# dust_environment_sensor_v2.net
KiCad netlist of a schematic drawn in EAGLE
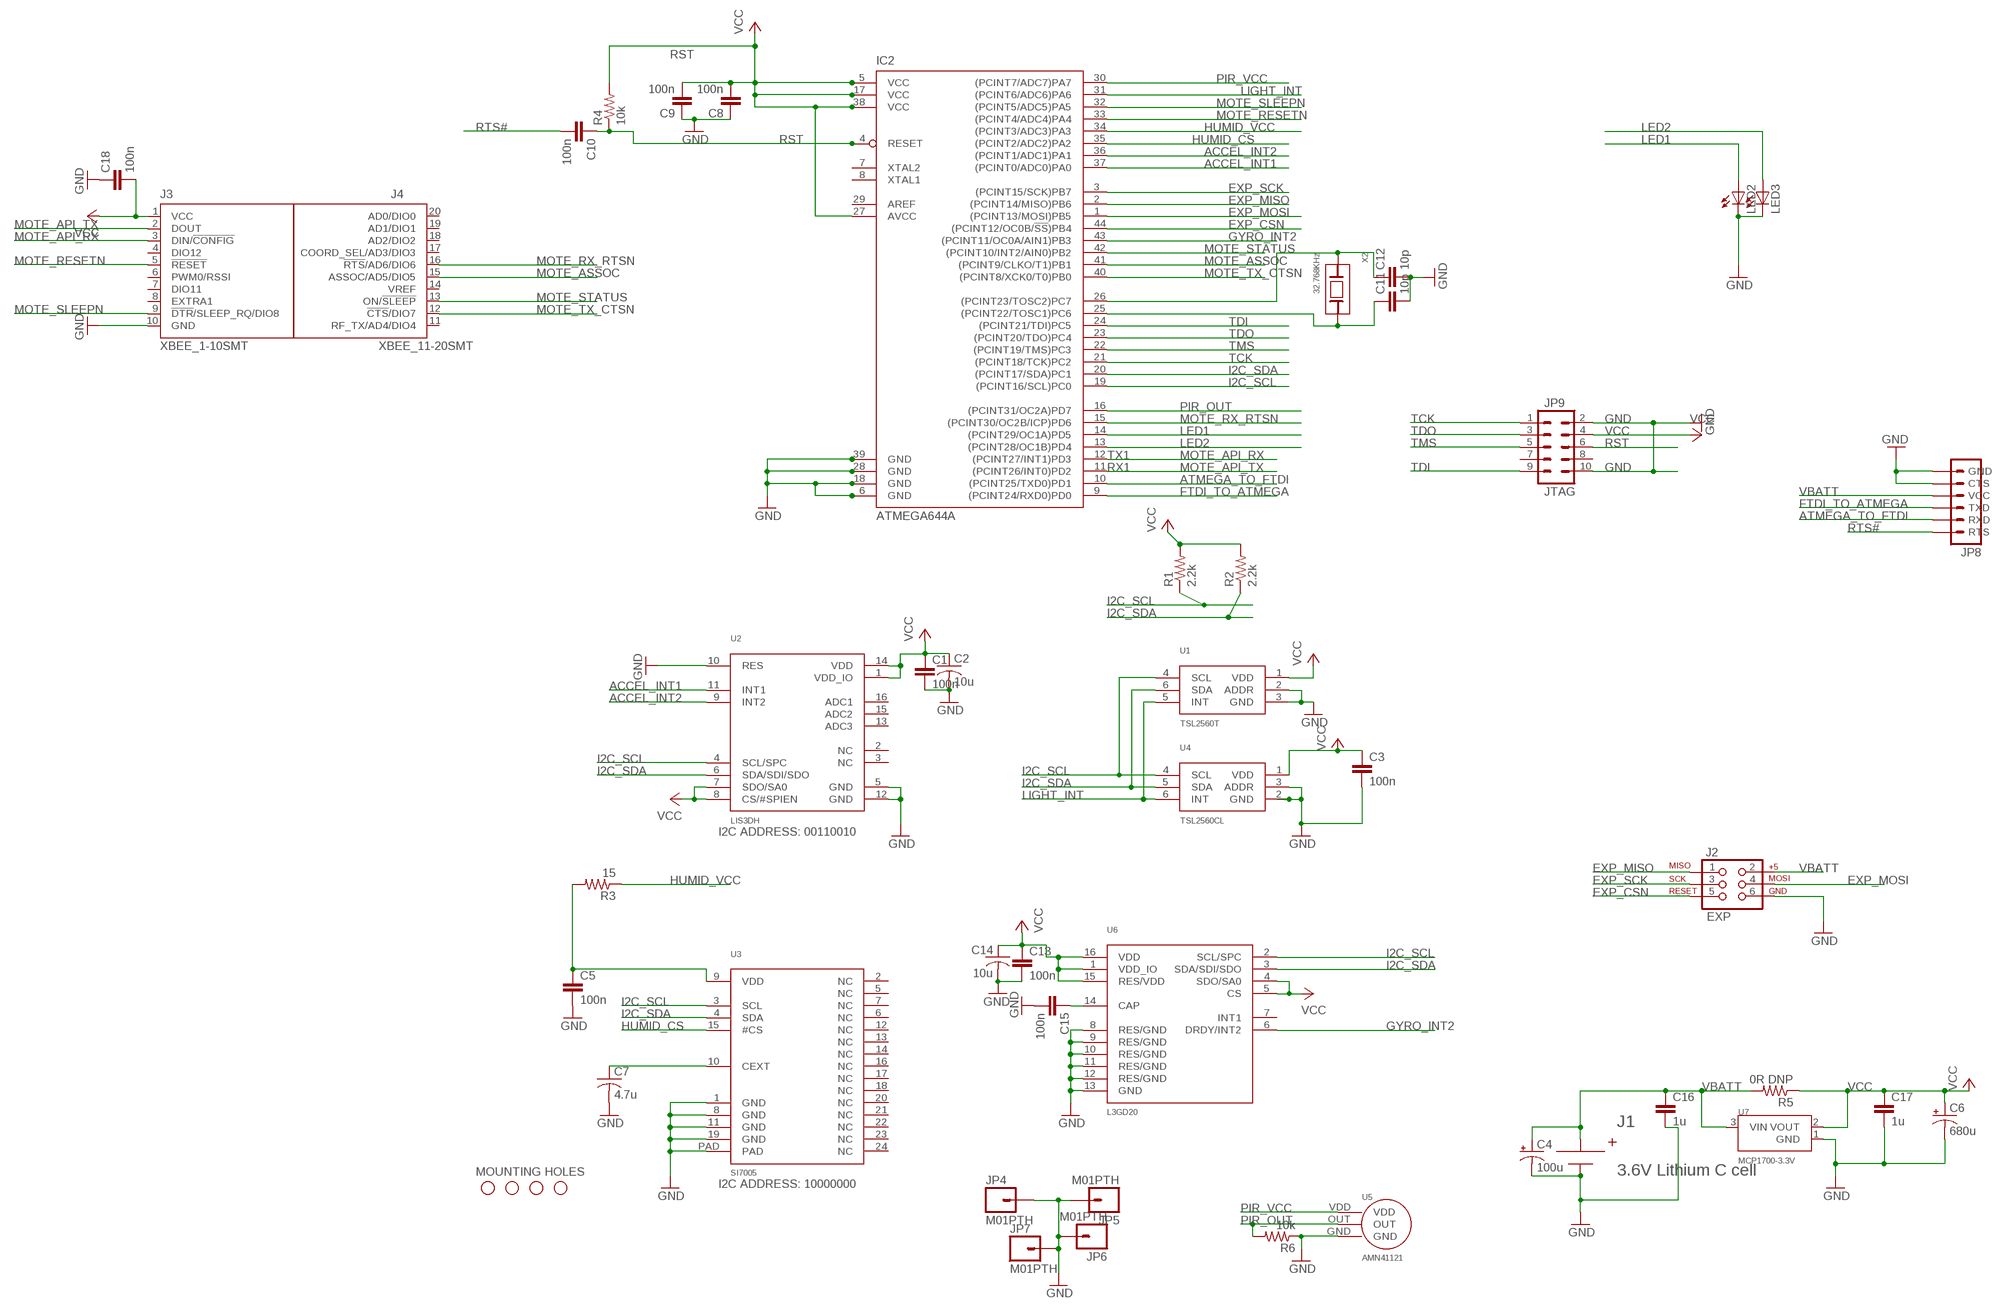
[diagram p0: schematic, sheet 1]

(export (version "E")
  (design (tool "Eeschema 10.0.6"))
  (components
    (comp (ref "C1")
      (value "100n")
      (footprint "eagle-import:C0603")
      (libsource (lib "eagle-import") (part "C-EUC0603"))
    )
    (comp (ref "C2")
      (value "10u")
      (footprint "eagle-import:C0603")
      (libsource (lib "eagle-import") (part "C-USC0603"))
    )
    (comp (ref "C3")
      (value "100n")
      (footprint "eagle-import:C0603")
      (libsource (lib "eagle-import") (part "C-EUC0603"))
    )
    (comp (ref "C4")
      (value "100u")
      (footprint "eagle-import:EIA3216-KIT")
      (libsource (lib "eagle-import") (part "CAP_POL1206-KIT"))
    )
    (comp (ref "C5")
      (value "100n")
      (footprint "eagle-import:C0603")
      (libsource (lib "eagle-import") (part "C-EUC0603"))
    )
    (comp (ref "C6")
      (value "680u")
      (footprint "eagle-import:EIA7343")
      (libsource (lib "eagle-import") (part "CAP_POL7343"))
    )
    (comp (ref "C7")
      (value "4.7u")
      (footprint "eagle-import:C0603")
      (libsource (lib "eagle-import") (part "C-USC0603"))
    )
    (comp (ref "C8")
      (value "100n")
      (footprint "eagle-import:C0603")
      (libsource (lib "eagle-import") (part "C-EUC0603"))
    )
    (comp (ref "C9")
      (value "100n")
      (footprint "eagle-import:C0603")
      (libsource (lib "eagle-import") (part "C-EUC0603"))
    )
    (comp (ref "C10")
      (value "100n")
      (footprint "eagle-import:C0603")
      (libsource (lib "eagle-import") (part "C-EUC0603"))
    )
    (comp (ref "C11")
      (value "10p")
      (footprint "eagle-import:C0603")
      (libsource (lib "eagle-import") (part "C-EUC0603"))
    )
    (comp (ref "C12")
      (value "10p")
      (footprint "eagle-import:C0603")
      (libsource (lib "eagle-import") (part "C-EUC0603"))
    )
    (comp (ref "C13")
      (value "100n")
      (footprint "eagle-import:C0603")
      (libsource (lib "eagle-import") (part "C-EUC0603"))
    )
    (comp (ref "C14")
      (value "10u")
      (footprint "eagle-import:C0603")
      (libsource (lib "eagle-import") (part "C-USC0603"))
    )
    (comp (ref "C15")
      (value "100n")
      (footprint "eagle-import:C0603")
      (libsource (lib "eagle-import") (part "C-EUC0603"))
    )
    (comp (ref "C16")
      (value "1u")
      (footprint "eagle-import:C0603")
      (libsource (lib "eagle-import") (part "C-EUC0603"))
    )
    (comp (ref "C17")
      (value "1u")
      (footprint "eagle-import:C0603")
      (libsource (lib "eagle-import") (part "C-EUC0603"))
    )
    (comp (ref "C18")
      (value "100n")
      (footprint "eagle-import:C0603")
      (libsource (lib "eagle-import") (part "C-EUC0603"))
    )
    (comp (ref "IC2")
      (value "ATMEGA644A")
      (footprint "eagle-import:TQFP44")
      (fields (field (name "MPN") "ATMEGA644PV-10AU"))
      (libsource (lib "eagle-import") (part "ATMEGA644A"))
    )
    (comp (ref "J1")
      (value "3.6V Lithium C cell")
      (footprint "eagle-import:BX0036")
      (libsource (lib "eagle-import") (part "BX0036"))
    )
    (comp (ref "J2")
      (value "EXP")
      (footprint "eagle-import:2X3")
      (libsource (lib "eagle-import") (part "AVR_SPI_PRG_6PTH"))
    )
    (comp (ref "J3")
      (value "XBEE_1-10SMT")
      (footprint "eagle-import:XBEE_1-10_SMT")
      (libsource (lib "eagle-import") (part "XBEE_1-10SMT"))
    )
    (comp (ref "J4")
      (value "XBEE_11-20SMT")
      (footprint "eagle-import:XBEE_11-20_SMT")
      (libsource (lib "eagle-import") (part "XBEE_11-20SMT"))
    )
    (comp (ref "JP4")
      (value "M01PTH")
      (footprint "eagle-import:1X01")
      (libsource (lib "eagle-import") (part "M01PTH"))
    )
    (comp (ref "JP5")
      (value "M01PTH")
      (footprint "eagle-import:1X01")
      (libsource (lib "eagle-import") (part "M01PTH"))
    )
    (comp (ref "JP6")
      (value "M01PTH")
      (footprint "eagle-import:1X01")
      (libsource (lib "eagle-import") (part "M01PTH"))
    )
    (comp (ref "JP7")
      (value "M01PTH")
      (footprint "eagle-import:1X01")
      (libsource (lib "eagle-import") (part "M01PTH"))
    )
    (comp (ref "JP8")
      (value "FTDI_CABLESIP")
      (footprint "eagle-import:1X06")
      (libsource (lib "eagle-import") (part "FTDI_CABLESIP"))
    )
    (comp (ref "JP9")
      (value "JTAG")
      (footprint "eagle-import:AVR_ICSP")
      (libsource (lib "eagle-import") (part "M05X2PTH"))
    )
    (comp (ref "LED2")
      (value "LEDCHIPLED_0805")
      (footprint "eagle-import:CHIPLED_0805")
      (libsource (lib "eagle-import") (part "LEDCHIPLED_0805"))
    )
    (comp (ref "LED3")
      (value "LEDCHIPLED_0805")
      (footprint "eagle-import:CHIPLED_0805")
      (libsource (lib "eagle-import") (part "LEDCHIPLED_0805"))
    )
    (comp (ref "R1")
      (value "2.2k")
      (footprint "eagle-import:R0603")
      (libsource (lib "eagle-import") (part "R-US_R0603"))
    )
    (comp (ref "R2")
      (value "2.2k")
      (footprint "eagle-import:R0603")
      (libsource (lib "eagle-import") (part "R-US_R0603"))
    )
    (comp (ref "R3")
      (value "15")
      (footprint "eagle-import:R0603")
      (libsource (lib "eagle-import") (part "R-US_R0603"))
    )
    (comp (ref "R4")
      (value "10k")
      (footprint "eagle-import:R0603")
      (libsource (lib "eagle-import") (part "R-US_R0603"))
    )
    (comp (ref "R5")
      (value "0R DNP")
      (footprint "eagle-import:R0603")
      (libsource (lib "eagle-import") (part "R-US_R0603"))
    )
    (comp (ref "R6")
      (value "10k")
      (footprint "eagle-import:R0603")
      (libsource (lib "eagle-import") (part "R-US_R0603"))
    )
    (comp (ref "STANDOFF1")
      (value "STAND-OFF")
      (footprint "eagle-import:STAND-OFF")
      (libsource (lib "eagle-import") (part "STAND-OFF"))
    )
    (comp (ref "STANDOFF2")
      (value "STAND-OFF")
      (footprint "eagle-import:STAND-OFF")
      (libsource (lib "eagle-import") (part "STAND-OFF"))
    )
    (comp (ref "STANDOFF3")
      (value "STAND-OFF")
      (footprint "eagle-import:STAND-OFF")
      (libsource (lib "eagle-import") (part "STAND-OFF"))
    )
    (comp (ref "STANDOFF4")
      (value "STAND-OFF")
      (footprint "eagle-import:STAND-OFF")
      (libsource (lib "eagle-import") (part "STAND-OFF"))
    )
    (comp (ref "U1")
      (value "TSL2560T")
      (footprint "eagle-import:T_TAOS")
      (libsource (lib "eagle-import") (part "TSL2560T"))
    )
    (comp (ref "U2")
      (value "LIS3DH")
      (footprint "eagle-import:LGA16_ST")
      (libsource (lib "eagle-import") (part "LIS3DH"))
    )
    (comp (ref "U3")
      (value "SI7005")
      (footprint "eagle-import:QFN24_SILICON_LABS")
      (libsource (lib "eagle-import") (part "SI7005"))
    )
    (comp (ref "U4")
      (value "TSL2560CL")
      (footprint "eagle-import:CL6_TAOS")
      (libsource (lib "eagle-import") (part "TSL2560CL"))
    )
    (comp (ref "U5")
      (value "AMN41121")
      (footprint "eagle-import:AMN41121")
      (libsource (lib "eagle-import") (part "AMN41121"))
    )
    (comp (ref "U6")
      (value "L3GD20")
      (footprint "eagle-import:LGA16_4X4_ST")
      (libsource (lib "eagle-import") (part "L3GD20"))
    )
    (comp (ref "U7")
      (value "MCP1700-3.3V")
      (footprint "eagle-import:SOT23-3")
      (libsource (lib "eagle-import") (part "MCP1700"))
    )
    (comp (ref "X2")
      (value "32.768KHz")
      (footprint "eagle-import:ABS07")
      (libsource (lib "eagle-import") (part "XTALABS07"))
    )
  )
  (nets
    (net (code "1") (name "/ACCEL_INT1") (class "Default")
      (node (ref "IC2") (pin "37") (pinfunction "(PCINT0/ADC0)PA0_37") (pintype "bidirectional"))
      (node (ref "U2") (pin "11") (pinfunction "INT1_11") (pintype "bidirectional"))
    )
    (net (code "2") (name "/ACCEL_INT2") (class "Default")
      (node (ref "IC2") (pin "36") (pinfunction "(PCINT1/ADC1)PA1_36") (pintype "bidirectional"))
      (node (ref "U2") (pin "9") (pinfunction "INT2_9") (pintype "bidirectional"))
    )
    (net (code "3") (name "/ATMEGA_TO_FTDI") (class "Default")
      (node (ref "IC2") (pin "10") (pinfunction "(PCINT25/TXD0)PD1_10") (pintype "bidirectional"))
      (node (ref "JP8") (pin "5") (pinfunction "RXD_5") (pintype "passive"))
    )
    (net (code "4") (name "/EXP_CSN") (class "Default")
      (node (ref "IC2") (pin "44") (pinfunction "(PCINT12/OC0B/~{SS})PB4_44") (pintype "bidirectional"))
      (node (ref "J2") (pin "5") (pinfunction "5_5") (pintype "passive"))
    )
    (net (code "5") (name "/EXP_MISO") (class "Default")
      (node (ref "IC2") (pin "2") (pinfunction "(PCINT14/MISO)PB6_2") (pintype "bidirectional"))
      (node (ref "J2") (pin "1") (pinfunction "1_1") (pintype "passive"))
    )
    (net (code "6") (name "/EXP_MOSI") (class "Default")
      (node (ref "IC2") (pin "1") (pinfunction "(PCINT13/MOSI)PB5_1") (pintype "bidirectional"))
      (node (ref "J2") (pin "4") (pinfunction "4_4") (pintype "passive"))
    )
    (net (code "7") (name "/EXP_SCK") (class "Default")
      (node (ref "IC2") (pin "3") (pinfunction "(PCINT15/SCK)PB7_3") (pintype "bidirectional"))
      (node (ref "J2") (pin "3") (pinfunction "3_3") (pintype "passive"))
    )
    (net (code "8") (name "/FTDI_TO_ATMEGA") (class "Default")
      (node (ref "IC2") (pin "9") (pinfunction "(PCINT24/RXD0)PD0_9") (pintype "bidirectional"))
      (node (ref "JP8") (pin "4") (pinfunction "TXD_4") (pintype "passive"))
    )
    (net (code "9") (name "/GYRO_INT2") (class "Default")
      (node (ref "IC2") (pin "43") (pinfunction "(PCINT11/OC0A/AIN1)PB3_43") (pintype "bidirectional"))
      (node (ref "U6") (pin "6") (pinfunction "DRDY/INT2_6") (pintype "bidirectional"))
    )
    (net (code "10") (name "/HUMID_CS") (class "Default")
      (node (ref "IC2") (pin "35") (pinfunction "(PCINT2/ADC2)PA2_35") (pintype "bidirectional"))
      (node (ref "U3") (pin "15") (pinfunction "#CS_15") (pintype "bidirectional"))
    )
    (net (code "11") (name "/HUMID_VCC") (class "Default")
      (node (ref "IC2") (pin "34") (pinfunction "(PCINT3/ADC3)PA3_34") (pintype "bidirectional"))
      (node (ref "R3") (pin "1") (pinfunction "1_1") (pintype "passive"))
    )
    (net (code "12") (name "/I2C_SCL") (class "Default")
      (node (ref "IC2") (pin "19") (pinfunction "(PCINT16/SCL)PC0_19") (pintype "output"))
      (node (ref "R1") (pin "1") (pinfunction "1_1") (pintype "passive"))
      (node (ref "U1") (pin "4") (pinfunction "SCL_4") (pintype "bidirectional"))
      (node (ref "U2") (pin "4") (pinfunction "SCL/SPC_4") (pintype "bidirectional"))
      (node (ref "U3") (pin "3") (pinfunction "SCL_3") (pintype "bidirectional"))
      (node (ref "U4") (pin "4") (pinfunction "SCL_4") (pintype "bidirectional"))
      (node (ref "U6") (pin "2") (pinfunction "SCL/SPC_2") (pintype "bidirectional"))
    )
    (net (code "13") (name "/I2C_SDA") (class "Default")
      (node (ref "IC2") (pin "20") (pinfunction "(PCINT17/SDA)PC1_20") (pintype "output"))
      (node (ref "R2") (pin "1") (pinfunction "1_1") (pintype "passive"))
      (node (ref "U1") (pin "6") (pinfunction "SDA_6") (pintype "bidirectional"))
      (node (ref "U2") (pin "6") (pinfunction "SDA/SDI/SDO_6") (pintype "bidirectional"))
      (node (ref "U3") (pin "4") (pinfunction "SDA_4") (pintype "bidirectional"))
      (node (ref "U4") (pin "5") (pinfunction "SDA_5") (pintype "bidirectional"))
      (node (ref "U6") (pin "3") (pinfunction "SDA/SDI/SDO_3") (pintype "bidirectional"))
    )
    (net (code "14") (name "/LED1") (class "Default")
      (node (ref "IC2") (pin "14") (pinfunction "(PCINT29/OC1A)PD5_14") (pintype "bidirectional"))
      (node (ref "LED2") (pin "A") (pinfunction "A_A") (pintype "passive"))
    )
    (net (code "15") (name "/LED2") (class "Default")
      (node (ref "IC2") (pin "13") (pinfunction "(PCINT28/OC1B)PD4_13") (pintype "bidirectional"))
      (node (ref "LED3") (pin "A") (pinfunction "A_A") (pintype "passive"))
    )
    (net (code "16") (name "/LIGHT_INT") (class "Default")
      (node (ref "IC2") (pin "31") (pinfunction "(PCINT6/ADC6)PA6_31") (pintype "bidirectional"))
      (node (ref "U1") (pin "5") (pinfunction "INT_5") (pintype "bidirectional"))
      (node (ref "U4") (pin "6") (pinfunction "INT_6") (pintype "bidirectional"))
    )
    (net (code "17") (name "/MOTE_API_RX") (class "Default")
      (node (ref "IC2") (pin "12") (pinfunction "(PCINT27/INT1)PD3_12") (pintype "bidirectional"))
      (node (ref "J3") (pin "3") (pinfunction "DIN/~{CONFIG}_3") (pintype "input"))
    )
    (net (code "18") (name "/MOTE_API_TX") (class "Default")
      (node (ref "IC2") (pin "11") (pinfunction "(PCINT26/INT0)PD2_11") (pintype "bidirectional"))
      (node (ref "J3") (pin "2") (pinfunction "DOUT_2") (pintype "output"))
    )
    (net (code "19") (name "/MOTE_ASSOC") (class "Default")
      (node (ref "IC2") (pin "41") (pinfunction "(PCINT9/CLKO/T1)PB1_41") (pintype "bidirectional"))
      (node (ref "J4") (pin "15") (pinfunction "ASSOC/AD5/DIO5_15") (pintype "bidirectional"))
    )
    (net (code "20") (name "/MOTE_RESETN") (class "Default")
      (node (ref "IC2") (pin "33") (pinfunction "(PCINT4/ADC4)PA4_33") (pintype "bidirectional"))
      (node (ref "J3") (pin "5") (pinfunction "~{RESET}_5") (pintype "input"))
    )
    (net (code "21") (name "/MOTE_RX_RTSN") (class "Default")
      (node (ref "IC2") (pin "15") (pinfunction "(PCINT30/OC2B/ICP)PD6_15") (pintype "bidirectional"))
      (node (ref "J4") (pin "16") (pinfunction "~{RTS}/AD6/DIO6_16") (pintype "bidirectional"))
    )
    (net (code "22") (name "/MOTE_SLEEPN") (class "Default")
      (node (ref "IC2") (pin "32") (pinfunction "(PCINT5/ADC5)PA5_32") (pintype "bidirectional"))
      (node (ref "J3") (pin "9") (pinfunction "~{DTR}/SLEEP_RQ/DIO8_9") (pintype "bidirectional"))
    )
    (net (code "23") (name "/MOTE_STATUS") (class "Default")
      (node (ref "IC2") (pin "42") (pinfunction "(PCINT10/INT2/AIN0)PB2_42") (pintype "bidirectional"))
      (node (ref "J4") (pin "13") (pinfunction "ON/~{SLEEP}_13") (pintype "output"))
    )
    (net (code "24") (name "/MOTE_TX_CTSN") (class "Default")
      (node (ref "IC2") (pin "40") (pinfunction "(PCINT8/XCK0/T0)PB0_40") (pintype "bidirectional"))
      (node (ref "J4") (pin "12") (pinfunction "~{CTS}/DIO7_12") (pintype "bidirectional"))
    )
    (net (code "25") (name "/PIR_OUT") (class "Default")
      (node (ref "IC2") (pin "16") (pinfunction "(PCINT31/OC2A)PD7_16") (pintype "bidirectional"))
      (node (ref "R6") (pin "2") (pinfunction "2_2") (pintype "passive"))
      (node (ref "U5") (pin "OUT") (pinfunction "OUT_OUT") (pintype "bidirectional"))
    )
    (net (code "26") (name "/PIR_VCC") (class "Default")
      (node (ref "IC2") (pin "30") (pinfunction "(PCINT7/ADC7)PA7_30") (pintype "bidirectional"))
      (node (ref "U5") (pin "VDD") (pinfunction "VDD_VDD") (pintype "bidirectional"))
    )
    (net (code "27") (name "/RST") (class "Default")
      (node (ref "C10") (pin "1") (pinfunction "1_1") (pintype "passive"))
      (node (ref "IC2") (pin "4") (pinfunction "RESET_4") (pintype "input"))
      (node (ref "JP9") (pin "6") (pinfunction "6_6") (pintype "passive"))
      (node (ref "R4") (pin "1") (pinfunction "1_1") (pintype "passive"))
    )
    (net (code "28") (name "/RTS#") (class "Default")
      (node (ref "C10") (pin "2") (pinfunction "2_2") (pintype "passive"))
      (node (ref "JP8") (pin "6") (pinfunction "RTS_6") (pintype "passive"))
    )
    (net (code "29") (name "/TCK") (class "Default")
      (node (ref "IC2") (pin "21") (pinfunction "(PCINT18/TCK)PC2_21") (pintype "output"))
      (node (ref "JP9") (pin "1") (pinfunction "1_1") (pintype "passive"))
    )
    (net (code "30") (name "/TDI") (class "Default")
      (node (ref "IC2") (pin "24") (pinfunction "(PCINT21/TDI)PC5_24") (pintype "output"))
      (node (ref "JP9") (pin "9") (pinfunction "9_9") (pintype "passive"))
    )
    (net (code "31") (name "/TDO") (class "Default")
      (node (ref "IC2") (pin "23") (pinfunction "(PCINT20/TDO)PC4_23") (pintype "output"))
      (node (ref "JP9") (pin "3") (pinfunction "3_3") (pintype "passive"))
    )
    (net (code "32") (name "/TMS") (class "Default")
      (node (ref "IC2") (pin "22") (pinfunction "(PCINT19/TMS)PC3_22") (pintype "output"))
      (node (ref "JP9") (pin "5") (pinfunction "5_5") (pintype "passive"))
    )
    (net (code "33") (name "/VBATT") (class "Default")
      (node (ref "C16") (pin "1") (pinfunction "1_1") (pintype "passive"))
      (node (ref "C4") (pin "A") (pinfunction "+_A") (pintype "passive"))
      (node (ref "J1") (pin "POS") (pinfunction "POS_POS") (pintype "bidirectional"))
      (node (ref "J2") (pin "2") (pinfunction "2_2") (pintype "passive"))
      (node (ref "JP8") (pin "3") (pinfunction "VCC_3") (pintype "passive"))
      (node (ref "R5") (pin "2") (pinfunction "2_2") (pintype "passive"))
      (node (ref "U7") (pin "3") (pinfunction "VIN_3") (pintype "bidirectional"))
    )
    (net (code "34") (name "GND") (class "Default")
      (node (ref "C1") (pin "2") (pinfunction "2_2") (pintype "passive"))
      (node (ref "C11") (pin "2") (pinfunction "2_2") (pintype "passive"))
      (node (ref "C12") (pin "2") (pinfunction "2_2") (pintype "passive"))
      (node (ref "C13") (pin "2") (pinfunction "2_2") (pintype "passive"))
      (node (ref "C14") (pin "2") (pinfunction "2_2") (pintype "passive"))
      (node (ref "C15") (pin "2") (pinfunction "2_2") (pintype "passive"))
      (node (ref "C16") (pin "2") (pinfunction "2_2") (pintype "passive"))
      (node (ref "C17") (pin "2") (pinfunction "2_2") (pintype "passive"))
      (node (ref "C18") (pin "1") (pinfunction "1_1") (pintype "passive"))
      (node (ref "C2") (pin "2") (pinfunction "2_2") (pintype "passive"))
      (node (ref "C3") (pin "2") (pinfunction "2_2") (pintype "passive"))
      (node (ref "C4") (pin "C") (pinfunction "-_C") (pintype "passive"))
      (node (ref "C5") (pin "2") (pinfunction "2_2") (pintype "passive"))
      (node (ref "C6") (pin "C") (pinfunction "-_C") (pintype "passive"))
      (node (ref "C7") (pin "2") (pinfunction "2_2") (pintype "passive"))
      (node (ref "C8") (pin "1") (pinfunction "1_1") (pintype "passive"))
      (node (ref "C9") (pin "1") (pinfunction "1_1") (pintype "passive"))
      (node (ref "IC2") (pin "18") (pinfunction "GND_18") (pintype "power_in"))
      (node (ref "IC2") (pin "28") (pinfunction "GND_28") (pintype "power_in"))
      (node (ref "IC2") (pin "39") (pinfunction "GND_39") (pintype "power_in"))
      (node (ref "IC2") (pin "6") (pinfunction "GND_6") (pintype "power_in"))
      (node (ref "J1") (pin "NEG") (pinfunction "NEG_NEG") (pintype "bidirectional"))
      (node (ref "J2") (pin "6") (pinfunction "6_6") (pintype "passive"))
      (node (ref "J3") (pin "10") (pinfunction "GND_10") (pintype "power_in"))
      (node (ref "JP4") (pin "1") (pinfunction "1_1") (pintype "passive"))
      (node (ref "JP5") (pin "1") (pinfunction "1_1") (pintype "passive"))
      (node (ref "JP6") (pin "1") (pinfunction "1_1") (pintype "passive"))
      (node (ref "JP7") (pin "1") (pinfunction "1_1") (pintype "passive"))
      (node (ref "JP8") (pin "1") (pinfunction "GND_1") (pintype "passive"))
      (node (ref "JP8") (pin "2") (pinfunction "CTS_2") (pintype "passive"))
      (node (ref "JP9") (pin "10") (pinfunction "10_10") (pintype "passive"))
      (node (ref "JP9") (pin "2") (pinfunction "2_2") (pintype "passive"))
      (node (ref "LED2") (pin "C") (pinfunction "C_C") (pintype "passive"))
      (node (ref "LED3") (pin "C") (pinfunction "C_C") (pintype "passive"))
      (node (ref "R6") (pin "1") (pinfunction "1_1") (pintype "passive"))
      (node (ref "U1") (pin "2") (pinfunction "ADDR_2") (pintype "bidirectional"))
      (node (ref "U1") (pin "3") (pinfunction "GND_3") (pintype "bidirectional"))
      (node (ref "U2") (pin "10") (pinfunction "RES_10") (pintype "bidirectional"))
      (node (ref "U2") (pin "12") (pinfunction "GND_12") (pintype "bidirectional"))
      (node (ref "U2") (pin "5") (pinfunction "GND_5") (pintype "bidirectional"))
      (node (ref "U3") (pin "1") (pinfunction "GND_1") (pintype "bidirectional"))
      (node (ref "U3") (pin "11") (pinfunction "GND_11") (pintype "bidirectional"))
      (node (ref "U3") (pin "19") (pinfunction "GND_19") (pintype "bidirectional"))
      (node (ref "U3") (pin "8") (pinfunction "GND_8") (pintype "bidirectional"))
      (node (ref "U3") (pin "PAD") (pinfunction "PAD_PAD") (pintype "bidirectional"))
      (node (ref "U4") (pin "2") (pinfunction "GND_2") (pintype "bidirectional"))
      (node (ref "U4") (pin "3") (pinfunction "ADDR_3") (pintype "bidirectional"))
      (node (ref "U5") (pin "GND") (pinfunction "GND_GND") (pintype "bidirectional"))
      (node (ref "U6") (pin "10") (pinfunction "RES/GND_10") (pintype "bidirectional"))
      (node (ref "U6") (pin "11") (pinfunction "RES/GND_11") (pintype "bidirectional"))
      (node (ref "U6") (pin "12") (pinfunction "RES/GND_12") (pintype "bidirectional"))
      (node (ref "U6") (pin "13") (pinfunction "GND_13") (pintype "bidirectional"))
      (node (ref "U6") (pin "8") (pinfunction "RES/GND_8") (pintype "bidirectional"))
      (node (ref "U6") (pin "9") (pinfunction "RES/GND_9") (pintype "bidirectional"))
      (node (ref "U7") (pin "1") (pinfunction "GND_1") (pintype "bidirectional"))
    )
    (net (code "35") (name "Net-(IC2-(PCINT22{slash}TOSC1)PC6)") (class "Default")
      (node (ref "C11") (pin "1") (pinfunction "1_1") (pintype "passive"))
      (node (ref "IC2") (pin "25") (pinfunction "(PCINT22/TOSC1)PC6_25") (pintype "output"))
      (node (ref "X2") (pin "2") (pinfunction "B_2") (pintype "bidirectional"))
    )
    (net (code "36") (name "Net-(IC2-(PCINT23{slash}TOSC2)PC7)") (class "Default")
      (node (ref "C12") (pin "1") (pinfunction "1_1") (pintype "passive"))
      (node (ref "IC2") (pin "26") (pinfunction "(PCINT23/TOSC2)PC7_26") (pintype "output"))
      (node (ref "X2") (pin "1") (pinfunction "A_1") (pintype "bidirectional"))
    )
    (net (code "37") (name "Net-(U3-CEXT)") (class "Default")
      (node (ref "C7") (pin "1") (pinfunction "1_1") (pintype "passive"))
      (node (ref "U3") (pin "10") (pinfunction "CEXT_10") (pintype "bidirectional"))
    )
    (net (code "38") (name "Net-(U3-VDD)") (class "Default")
      (node (ref "C5") (pin "1") (pinfunction "1_1") (pintype "passive"))
      (node (ref "R3") (pin "2") (pinfunction "2_2") (pintype "passive"))
      (node (ref "U3") (pin "9") (pinfunction "VDD_9") (pintype "bidirectional"))
    )
    (net (code "39") (name "Net-(U6-CAP)") (class "Default")
      (node (ref "C15") (pin "1") (pinfunction "1_1") (pintype "passive"))
      (node (ref "U6") (pin "14") (pinfunction "CAP_14") (pintype "bidirectional"))
    )
    (net (code "40") (name "VCC") (class "Default")
      (node (ref "C1") (pin "1") (pinfunction "1_1") (pintype "passive"))
      (node (ref "C13") (pin "1") (pinfunction "1_1") (pintype "passive"))
      (node (ref "C14") (pin "1") (pinfunction "1_1") (pintype "passive"))
      (node (ref "C17") (pin "1") (pinfunction "1_1") (pintype "passive"))
      (node (ref "C18") (pin "2") (pinfunction "2_2") (pintype "passive"))
      (node (ref "C2") (pin "1") (pinfunction "1_1") (pintype "passive"))
      (node (ref "C3") (pin "1") (pinfunction "1_1") (pintype "passive"))
      (node (ref "C6") (pin "A") (pinfunction "+_A") (pintype "passive"))
      (node (ref "C8") (pin "2") (pinfunction "2_2") (pintype "passive"))
      (node (ref "C9") (pin "2") (pinfunction "2_2") (pintype "passive"))
      (node (ref "IC2") (pin "17") (pinfunction "VCC_17") (pintype "power_in"))
      (node (ref "IC2") (pin "27") (pinfunction "AVCC_27") (pintype "power_in"))
      (node (ref "IC2") (pin "38") (pinfunction "VCC_38") (pintype "power_in"))
      (node (ref "IC2") (pin "5") (pinfunction "VCC_5") (pintype "power_in"))
      (node (ref "J3") (pin "1") (pinfunction "VCC_1") (pintype "power_in"))
      (node (ref "JP9") (pin "4") (pinfunction "4_4") (pintype "passive"))
      (node (ref "R1") (pin "2") (pinfunction "2_2") (pintype "passive"))
      (node (ref "R2") (pin "2") (pinfunction "2_2") (pintype "passive"))
      (node (ref "R4") (pin "2") (pinfunction "2_2") (pintype "passive"))
      (node (ref "R5") (pin "1") (pinfunction "1_1") (pintype "passive"))
      (node (ref "U1") (pin "1") (pinfunction "VDD_1") (pintype "bidirectional"))
      (node (ref "U2") (pin "1") (pinfunction "VDD_IO_1") (pintype "bidirectional"))
      (node (ref "U2") (pin "14") (pinfunction "VDD_14") (pintype "bidirectional"))
      (node (ref "U2") (pin "7") (pinfunction "SDO/SA0_7") (pintype "bidirectional"))
      (node (ref "U2") (pin "8") (pinfunction "CS/#SPIEN_8") (pintype "bidirectional"))
      (node (ref "U4") (pin "1") (pinfunction "VDD_1") (pintype "bidirectional"))
      (node (ref "U6") (pin "1") (pinfunction "VDD_IO_1") (pintype "bidirectional"))
      (node (ref "U6") (pin "15") (pinfunction "RES/VDD_15") (pintype "bidirectional"))
      (node (ref "U6") (pin "16") (pinfunction "VDD_16") (pintype "bidirectional"))
      (node (ref "U6") (pin "4") (pinfunction "SDO/SA0_4") (pintype "bidirectional"))
      (node (ref "U6") (pin "5") (pinfunction "CS_5") (pintype "bidirectional"))
      (node (ref "U7") (pin "2") (pinfunction "VOUT_2") (pintype "bidirectional"))
    )
    (net (code "41") (name "unconnected-(IC2-AREF-Pad29)") (class "Default")
      (node (ref "IC2") (pin "29") (pinfunction "AREF_29") (pintype "passive"))
    )
    (net (code "42") (name "unconnected-(IC2-XTAL1-Pad8)") (class "Default")
      (node (ref "IC2") (pin "8") (pinfunction "XTAL1_8") (pintype "bidirectional"))
    )
    (net (code "43") (name "unconnected-(IC2-XTAL2-Pad7)") (class "Default")
      (node (ref "IC2") (pin "7") (pinfunction "XTAL2_7") (pintype "bidirectional"))
    )
    (net (code "44") (name "unconnected-(J3-DIO11-Pad7)") (class "Default")
      (node (ref "J3") (pin "7") (pinfunction "DIO11_7") (pintype "output"))
    )
    (net (code "45") (name "unconnected-(J3-DIO12-Pad4)") (class "Default")
      (node (ref "J3") (pin "4") (pinfunction "DIO12_4") (pintype "bidirectional"))
    )
    (net (code "46") (name "unconnected-(J3-EXTRA1-Pad8)") (class "Default")
      (node (ref "J3") (pin "8") (pinfunction "EXTRA1_8") (pintype "bidirectional"))
    )
    (net (code "47") (name "unconnected-(J3-PWM0{slash}RSSI-Pad6)") (class "Default")
      (node (ref "J3") (pin "6") (pinfunction "PWM0/RSSI_6") (pintype "output"))
    )
    (net (code "48") (name "unconnected-(J4-AD0{slash}DIO0-Pad20)") (class "Default")
      (node (ref "J4") (pin "20") (pinfunction "AD0/DIO0_20") (pintype "bidirectional"))
    )
    (net (code "49") (name "unconnected-(J4-AD1{slash}DIO1-Pad19)") (class "Default")
      (node (ref "J4") (pin "19") (pinfunction "AD1/DIO1_19") (pintype "bidirectional"))
    )
    (net (code "50") (name "unconnected-(J4-AD2{slash}DIO2-Pad18)") (class "Default")
      (node (ref "J4") (pin "18") (pinfunction "AD2/DIO2_18") (pintype "bidirectional"))
    )
    (net (code "51") (name "unconnected-(J4-COORD_SEL{slash}AD3{slash}DIO3-Pad17)") (class "Default")
      (node (ref "J4") (pin "17") (pinfunction "COORD_SEL/AD3/DIO3_17") (pintype "bidirectional"))
    )
    (net (code "52") (name "unconnected-(J4-RF_TX{slash}AD4{slash}DIO4-Pad11)") (class "Default")
      (node (ref "J4") (pin "11") (pinfunction "RF_TX/AD4/DIO4_11") (pintype "bidirectional"))
    )
    (net (code "53") (name "unconnected-(J4-VREF-Pad14)") (class "Default")
      (node (ref "J4") (pin "14") (pinfunction "VREF_14") (pintype "input"))
    )
    (net (code "54") (name "unconnected-(JP9-Pad7)") (class "Default")
      (node (ref "JP9") (pin "7") (pinfunction "7_7") (pintype "passive"))
    )
    (net (code "55") (name "unconnected-(JP9-Pad8)") (class "Default")
      (node (ref "JP9") (pin "8") (pinfunction "8_8") (pintype "passive"))
    )
    (net (code "56") (name "unconnected-(U2-ADC1-Pad16)") (class "Default")
      (node (ref "U2") (pin "16") (pinfunction "ADC1_16") (pintype "bidirectional"))
    )
    (net (code "57") (name "unconnected-(U2-ADC2-Pad15)") (class "Default")
      (node (ref "U2") (pin "15") (pinfunction "ADC2_15") (pintype "bidirectional"))
    )
    (net (code "58") (name "unconnected-(U2-ADC3-Pad13)") (class "Default")
      (node (ref "U2") (pin "13") (pinfunction "ADC3_13") (pintype "bidirectional"))
    )
    (net (code "59") (name "unconnected-(U2-NC-Pad2)") (class "Default")
      (node (ref "U2") (pin "2") (pinfunction "NC_2") (pintype "bidirectional"))
    )
    (net (code "60") (name "unconnected-(U2-NC-Pad3)") (class "Default")
      (node (ref "U2") (pin "3") (pinfunction "NC_3") (pintype "bidirectional"))
    )
    (net (code "61") (name "unconnected-(U3-NC-Pad2)") (class "Default")
      (node (ref "U3") (pin "2") (pinfunction "NC_2") (pintype "bidirectional"))
    )
    (net (code "62") (name "unconnected-(U3-NC-Pad5)") (class "Default")
      (node (ref "U3") (pin "5") (pinfunction "NC_5") (pintype "bidirectional"))
    )
    (net (code "63") (name "unconnected-(U3-NC-Pad6)") (class "Default")
      (node (ref "U3") (pin "6") (pinfunction "NC_6") (pintype "bidirectional"))
    )
    (net (code "64") (name "unconnected-(U3-NC-Pad7)") (class "Default")
      (node (ref "U3") (pin "7") (pinfunction "NC_7") (pintype "bidirectional"))
    )
    (net (code "65") (name "unconnected-(U3-NC-Pad12)") (class "Default")
      (node (ref "U3") (pin "12") (pinfunction "NC_12") (pintype "bidirectional"))
    )
    (net (code "66") (name "unconnected-(U3-NC-Pad13)") (class "Default")
      (node (ref "U3") (pin "13") (pinfunction "NC_13") (pintype "bidirectional"))
    )
    (net (code "67") (name "unconnected-(U3-NC-Pad14)") (class "Default")
      (node (ref "U3") (pin "14") (pinfunction "NC_14") (pintype "bidirectional"))
    )
    (net (code "68") (name "unconnected-(U3-NC-Pad16)") (class "Default")
      (node (ref "U3") (pin "16") (pinfunction "NC_16") (pintype "bidirectional"))
    )
    (net (code "69") (name "unconnected-(U3-NC-Pad17)") (class "Default")
      (node (ref "U3") (pin "17") (pinfunction "NC_17") (pintype "bidirectional"))
    )
    (net (code "70") (name "unconnected-(U3-NC-Pad18)") (class "Default")
      (node (ref "U3") (pin "18") (pinfunction "NC_18") (pintype "bidirectional"))
    )
    (net (code "71") (name "unconnected-(U3-NC-Pad20)") (class "Default")
      (node (ref "U3") (pin "20") (pinfunction "NC_20") (pintype "bidirectional"))
    )
    (net (code "72") (name "unconnected-(U3-NC-Pad21)") (class "Default")
      (node (ref "U3") (pin "21") (pinfunction "NC_21") (pintype "bidirectional"))
    )
    (net (code "73") (name "unconnected-(U3-NC-Pad22)") (class "Default")
      (node (ref "U3") (pin "22") (pinfunction "NC_22") (pintype "bidirectional"))
    )
    (net (code "74") (name "unconnected-(U3-NC-Pad23)") (class "Default")
      (node (ref "U3") (pin "23") (pinfunction "NC_23") (pintype "bidirectional"))
    )
    (net (code "75") (name "unconnected-(U3-NC-Pad24)") (class "Default")
      (node (ref "U3") (pin "24") (pinfunction "NC_24") (pintype "bidirectional"))
    )
    (net (code "76") (name "unconnected-(U6-INT1-Pad7)") (class "Default")
      (node (ref "U6") (pin "7") (pinfunction "INT1_7") (pintype "bidirectional"))
    )
  )
)
